# Connectors.net
KiCad netlist of a schematic drawn in Altium Designer
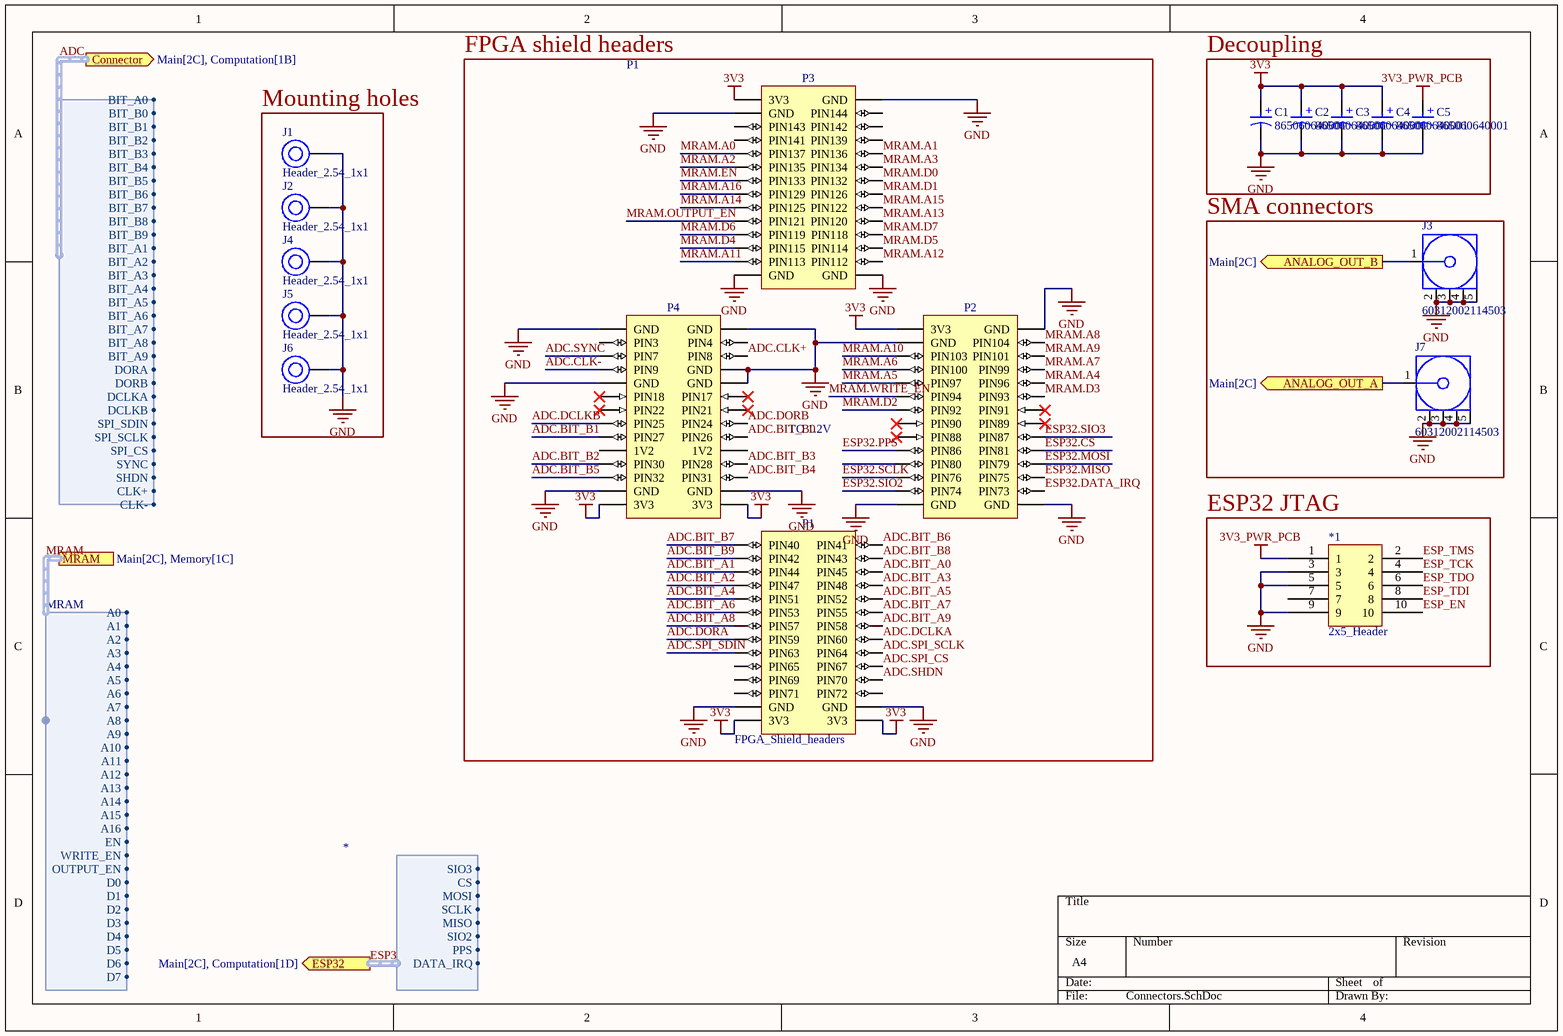
[diagram p0: Connectors.SchDoc]

(export (version "E")
  (design (tool "Eeschema 10.0.6"))
  (components
    (comp (ref "*1")
      (value "2x5_Header")
      (footprint "2x5_HEADER")
      (libsource (lib "Schlib1") (part "2x5_Header"))
    )
    (comp (ref "C1")
      (value "865060640001")
      (footprint "WCAP-ASLL_D4H5.5")
      (description "865060640001 WCAP-ASLL Aluminum Electrolytic Capacitors")
      (fields (field (name "TOLERANCE") "20%"))
      (libsource (lib "Altium Content Vault") (part "Capacitor_Polarized"))
    )
    (comp (ref "C2")
      (value "865060640001")
      (footprint "WCAP-ASLL_D4H5.5")
      (description "865060640001 WCAP-ASLL Aluminum Electrolytic Capacitors")
      (fields (field (name "TOLERANCE") "20%"))
      (libsource (lib "Altium Content Vault") (part "Capacitor_Polarized"))
    )
    (comp (ref "C3")
      (value "865060640001")
      (footprint "WCAP-ASLL_D4H5.5")
      (description "865060640001 WCAP-ASLL Aluminum Electrolytic Capacitors")
      (fields (field (name "TOLERANCE") "20%"))
      (libsource (lib "Altium Content Vault") (part "Capacitor_Polarized"))
    )
    (comp (ref "C4")
      (value "865060640001")
      (footprint "WCAP-ASLL_D4H5.5")
      (description "865060640001 WCAP-ASLL Aluminum Electrolytic Capacitors")
      (fields (field (name "TOLERANCE") "20%"))
      (libsource (lib "Altium Content Vault") (part "Capacitor_Polarized"))
    )
    (comp (ref "C5")
      (value "865060640001")
      (footprint "WCAP-ASLL_D4H5.5")
      (description "865060640001 WCAP-ASLL Aluminum Electrolytic Capacitors")
      (fields (field (name "TOLERANCE") "20%"))
      (libsource (lib "Altium Content Vault") (part "Capacitor_Polarized"))
    )
    (comp (ref "J1")
      (value "Header_2.54_1x1")
      (footprint "HEADER_2.54_1x1")
      (description "Header 1x1")
      (libsource (lib "Schlib1") (part "Header_2.54_1x1"))
    )
    (comp (ref "J2")
      (value "Header_2.54_1x1")
      (footprint "HEADER_2.54_1x1")
      (description "Header 1x1")
      (libsource (lib "Schlib1") (part "Header_2.54_1x1"))
    )
    (comp (ref "J3")
      (value "60312002114503")
      (footprint "60312002114503")
      (description "SMA PCB THT JACK STRAIGHT WR-SMA")
      (libsource (lib "Altium Content Vault") (part "Jack_4GND"))
    )
    (comp (ref "J4")
      (value "Header_2.54_1x1")
      (footprint "HEADER_2.54_1x1")
      (description "Header 1x1")
      (libsource (lib "Schlib1") (part "Header_2.54_1x1"))
    )
    (comp (ref "J5")
      (value "Header_2.54_1x1")
      (footprint "HEADER_2.54_1x1")
      (description "Header 1x1")
      (libsource (lib "Schlib1") (part "Header_2.54_1x1"))
    )
    (comp (ref "J6")
      (value "Header_2.54_1x1")
      (footprint "HEADER_2.54_1x1")
      (description "Header 1x1")
      (libsource (lib "Schlib1") (part "Header_2.54_1x1"))
    )
    (comp (ref "J7")
      (value "60312002114503")
      (footprint "60312002114503")
      (description "SMA PCB THT JACK STRAIGHT WR-SMA")
      (libsource (lib "Altium Content Vault") (part "Jack_4GND"))
    )
    (comp (ref "P1")
      (value "FPGA_Shield_headers")
      (footprint "FPGA_SHIELD_HEADER_FOOTPRINT")
      (libsource (lib "Schlib1") (part "FPGA_Shield_headers"))
    )
  )
  (nets
    (net (code "4") (name "/ADC.BIT_A0") (class "Default")
      (node (ref "P1") (pin "90") (pinfunction "PIN45_90") (pintype "bidirectional"))
    )
    (net (code "5") (name "/ADC.BIT_A1") (class "Default")
      (node (ref "P1") (pin "89") (pinfunction "PIN44_89") (pintype "bidirectional"))
    )
    (net (code "6") (name "/ADC.BIT_A2") (class "Default")
      (node (ref "P1") (pin "91") (pinfunction "PIN47_91") (pintype "bidirectional"))
    )
    (net (code "7") (name "/ADC.BIT_A3") (class "Default")
      (node (ref "P1") (pin "92") (pinfunction "PIN48_92") (pintype "bidirectional"))
    )
    (net (code "8") (name "/ADC.BIT_A4") (class "Default")
      (node (ref "P1") (pin "93") (pinfunction "PIN51_93") (pintype "bidirectional"))
    )
    (net (code "9") (name "/ADC.BIT_A5") (class "Default")
      (node (ref "P1") (pin "94") (pinfunction "PIN52_94") (pintype "bidirectional"))
    )
    (net (code "10") (name "/ADC.BIT_A6") (class "Default")
      (node (ref "P1") (pin "95") (pinfunction "PIN53_95") (pintype "bidirectional"))
    )
    (net (code "11") (name "/ADC.BIT_A7") (class "Default")
      (node (ref "P1") (pin "96") (pinfunction "PIN55_96") (pintype "bidirectional"))
    )
    (net (code "12") (name "/ADC.BIT_A8") (class "Default")
      (node (ref "P1") (pin "97") (pinfunction "PIN57_97") (pintype "bidirectional"))
    )
    (net (code "13") (name "/ADC.BIT_A9") (class "Default")
      (node (ref "P1") (pin "98") (pinfunction "PIN58_98") (pintype "bidirectional"))
    )
    (net (code "14") (name "/ADC.BIT_B0") (class "Default")
      (node (ref "P1") (pin "18") (pinfunction "PIN26_18") (pintype "bidirectional"))
    )
    (net (code "15") (name "/ADC.BIT_B1") (class "Default")
      (node (ref "P1") (pin "17") (pinfunction "PIN27_17") (pintype "bidirectional"))
    )
    (net (code "16") (name "/ADC.BIT_B2") (class "Default")
      (node (ref "P1") (pin "21") (pinfunction "PIN30_21") (pintype "bidirectional"))
    )
    (net (code "17") (name "/ADC.BIT_B3") (class "Default")
      (node (ref "P1") (pin "22") (pinfunction "PIN28_22") (pintype "bidirectional"))
    )
    (net (code "18") (name "/ADC.BIT_B4") (class "Default")
      (node (ref "P1") (pin "24") (pinfunction "PIN31_24") (pintype "bidirectional"))
    )
    (net (code "19") (name "/ADC.BIT_B5") (class "Default")
      (node (ref "P1") (pin "23") (pinfunction "PIN32_23") (pintype "bidirectional"))
    )
    (net (code "20") (name "/ADC.BIT_B6") (class "Default")
      (node (ref "P1") (pin "86") (pinfunction "PIN41_86") (pintype "bidirectional"))
    )
    (net (code "21") (name "/ADC.BIT_B7") (class "Default")
      (node (ref "P1") (pin "85") (pinfunction "PIN40_85") (pintype "bidirectional"))
    )
    (net (code "22") (name "/ADC.BIT_B8") (class "Default")
      (node (ref "P1") (pin "88") (pinfunction "PIN43_88") (pintype "bidirectional"))
    )
    (net (code "23") (name "/ADC.BIT_B9") (class "Default")
      (node (ref "P1") (pin "87") (pinfunction "PIN42_87") (pintype "bidirectional"))
    )
    (net (code "24") (name "/ADC.CLK+") (class "Default")
      (node (ref "P1") (pin "6") (pinfunction "PIN8_6") (pintype "bidirectional"))
    )
    (net (code "25") (name "/ADC.CLK-") (class "Default")
      (node (ref "P1") (pin "7") (pinfunction "PIN9_7") (pintype "bidirectional"))
    )
    (net (code "26") (name "/ADC.DCLKA") (class "Default")
      (node (ref "P1") (pin "100") (pinfunction "PIN60_100") (pintype "bidirectional"))
    )
    (net (code "27") (name "/ADC.DCLKB") (class "Default")
      (node (ref "P1") (pin "15") (pinfunction "PIN25_15") (pintype "bidirectional"))
    )
    (net (code "28") (name "/ADC.DORA") (class "Default")
      (node (ref "P1") (pin "99") (pinfunction "PIN59_99") (pintype "bidirectional"))
    )
    (net (code "29") (name "/ADC.DORB") (class "Default")
      (node (ref "P1") (pin "16") (pinfunction "PIN24_16") (pintype "bidirectional"))
    )
    (net (code "30") (name "/ADC.SHDN") (class "Default")
      (node (ref "P1") (pin "106") (pinfunction "PIN70_106") (pintype "bidirectional"))
    )
    (net (code "31") (name "/ADC.SPI_CS") (class "Default")
      (node (ref "P1") (pin "104") (pinfunction "PIN67_104") (pintype "bidirectional"))
    )
    (net (code "32") (name "/ADC.SPI_SCLK") (class "Default")
      (node (ref "P1") (pin "102") (pinfunction "PIN64_102") (pintype "bidirectional"))
    )
    (net (code "33") (name "/ADC.SPI_SDIN") (class "Default")
      (node (ref "P1") (pin "101") (pinfunction "PIN63_101") (pintype "bidirectional"))
    )
    (net (code "34") (name "/ADC.SYNC") (class "Default")
      (node (ref "P1") (pin "5") (pinfunction "PIN7_5") (pintype "bidirectional"))
    )
    (net (code "36") (name "/ANALOG_OUT_A") (class "Default")
      (node (ref "J7") (pin "1") (pinfunction "Signal_1") (pintype "passive"))
    )
    (net (code "37") (name "/ANALOG_OUT_B") (class "Default")
      (node (ref "J3") (pin "1") (pinfunction "Signal_1") (pintype "passive"))
    )
    (net (code "38") (name "/ESP32.CS") (class "Default")
      (node (ref "P1") (pin "76") (pinfunction "PIN81_76") (pintype "bidirectional"))
    )
    (net (code "39") (name "/ESP32.DATA_IRQ") (class "Default")
      (node (ref "P1") (pin "82") (pinfunction "PIN73_82") (pintype "bidirectional"))
    )
    (net (code "40") (name "/ESP32.MISO") (class "Default")
      (node (ref "P1") (pin "80") (pinfunction "PIN75_80") (pintype "bidirectional"))
    )
    (net (code "41") (name "/ESP32.MOSI") (class "Default")
      (node (ref "P1") (pin "78") (pinfunction "PIN79_78") (pintype "bidirectional"))
    )
    (net (code "42") (name "/ESP32.PPS") (class "Default")
      (node (ref "P1") (pin "75") (pinfunction "PIN86_75") (pintype "bidirectional"))
    )
    (net (code "43") (name "/ESP32.SCLK") (class "Default")
      (node (ref "P1") (pin "79") (pinfunction "PIN76_79") (pintype "bidirectional"))
    )
    (net (code "44") (name "/ESP32.SIO2") (class "Default")
      (node (ref "P1") (pin "81") (pinfunction "PIN74_81") (pintype "bidirectional"))
    )
    (net (code "45") (name "/ESP32.SIO3") (class "Default")
      (node (ref "P1") (pin "74") (pinfunction "PIN87_74") (pintype "bidirectional"))
    )
    (net (code "47") (name "/ESP_EN") (class "Default")
      (node (ref "*1") (pin "10") (pinfunction "10_10") (pintype "passive"))
    )
    (net (code "48") (name "/ESP_TCK") (class "Default")
      (node (ref "*1") (pin "4") (pinfunction "4_4") (pintype "passive"))
    )
    (net (code "49") (name "/ESP_TDI") (class "Default")
      (node (ref "*1") (pin "8") (pinfunction "8_8") (pintype "passive"))
    )
    (net (code "50") (name "/ESP_TDO") (class "Default")
      (node (ref "*1") (pin "6") (pinfunction "6_6") (pintype "passive"))
    )
    (net (code "51") (name "/ESP_TMS") (class "Default")
      (node (ref "*1") (pin "2") (pinfunction "2_2") (pintype "passive"))
    )
    (net (code "52") (name "/MRAM.A0") (class "Default")
      (node (ref "P1") (pin "37") (pinfunction "PIN137_37") (pintype "bidirectional"))
    )
    (net (code "53") (name "/MRAM.A1") (class "Default")
      (node (ref "P1") (pin "38") (pinfunction "PIN136_38") (pintype "bidirectional"))
    )
    (net (code "54") (name "/MRAM.A2") (class "Default")
      (node (ref "P1") (pin "39") (pinfunction "PIN135_39") (pintype "bidirectional"))
    )
    (net (code "55") (name "/MRAM.A3") (class "Default")
      (node (ref "P1") (pin "40") (pinfunction "PIN134_40") (pintype "bidirectional"))
    )
    (net (code "56") (name "/MRAM.A4") (class "Default")
      (node (ref "P1") (pin "66") (pinfunction "PIN96_66") (pintype "bidirectional"))
    )
    (net (code "57") (name "/MRAM.A5") (class "Default")
      (node (ref "P1") (pin "65") (pinfunction "PIN97_65") (pintype "bidirectional"))
    )
    (net (code "58") (name "/MRAM.A6") (class "Default")
      (node (ref "P1") (pin "63") (pinfunction "PIN100_63") (pintype "bidirectional"))
    )
    (net (code "59") (name "/MRAM.A7") (class "Default")
      (node (ref "P1") (pin "64") (pinfunction "PIN99_64") (pintype "bidirectional"))
    )
    (net (code "60") (name "/MRAM.A8") (class "Default")
      (node (ref "P1") (pin "60") (pinfunction "PIN104_60") (pintype "bidirectional"))
    )
    (net (code "61") (name "/MRAM.A9") (class "Default")
      (node (ref "P1") (pin "62") (pinfunction "PIN101_62") (pintype "bidirectional"))
    )
    (net (code "62") (name "/MRAM.A10") (class "Default")
      (node (ref "P1") (pin "61") (pinfunction "PIN103_61") (pintype "bidirectional"))
    )
    (net (code "63") (name "/MRAM.A11") (class "Default")
      (node (ref "P1") (pin "53") (pinfunction "PIN113_53") (pintype "bidirectional"))
    )
    (net (code "64") (name "/MRAM.A12") (class "Default")
      (node (ref "P1") (pin "54") (pinfunction "PIN112_54") (pintype "bidirectional"))
    )
    (net (code "65") (name "/MRAM.A13") (class "Default")
      (node (ref "P1") (pin "48") (pinfunction "PIN120_48") (pintype "bidirectional"))
    )
    (net (code "66") (name "/MRAM.A14") (class "Default")
      (node (ref "P1") (pin "45") (pinfunction "PIN125_45") (pintype "bidirectional"))
    )
    (net (code "67") (name "/MRAM.A15") (class "Default")
      (node (ref "P1") (pin "46") (pinfunction "PIN122_46") (pintype "bidirectional"))
    )
    (net (code "68") (name "/MRAM.A16") (class "Default")
      (node (ref "P1") (pin "43") (pinfunction "PIN129_43") (pintype "bidirectional"))
    )
    (net (code "69") (name "/MRAM.D0") (class "Default")
      (node (ref "P1") (pin "42") (pinfunction "PIN132_42") (pintype "bidirectional"))
    )
    (net (code "70") (name "/MRAM.D1") (class "Default")
      (node (ref "P1") (pin "44") (pinfunction "PIN126_44") (pintype "bidirectional"))
    )
    (net (code "71") (name "/MRAM.D2") (class "Default")
      (node (ref "P1") (pin "69") (pinfunction "PIN92_69") (pintype "bidirectional"))
    )
    (net (code "72") (name "/MRAM.D3") (class "Default")
      (node (ref "P1") (pin "68") (pinfunction "PIN93_68") (pintype "bidirectional"))
    )
    (net (code "73") (name "/MRAM.D4") (class "Default")
      (node (ref "P1") (pin "51") (pinfunction "PIN115_51") (pintype "bidirectional"))
    )
    (net (code "74") (name "/MRAM.D5") (class "Default")
      (node (ref "P1") (pin "52") (pinfunction "PIN114_52") (pintype "bidirectional"))
    )
    (net (code "75") (name "/MRAM.D6") (class "Default")
      (node (ref "P1") (pin "49") (pinfunction "PIN119_49") (pintype "bidirectional"))
    )
    (net (code "76") (name "/MRAM.D7") (class "Default")
      (node (ref "P1") (pin "50") (pinfunction "PIN118_50") (pintype "bidirectional"))
    )
    (net (code "77") (name "/MRAM.EN") (class "Default")
      (node (ref "P1") (pin "41") (pinfunction "PIN133_41") (pintype "bidirectional"))
    )
    (net (code "78") (name "/MRAM.OUTPUT_EN") (class "Default")
      (node (ref "P1") (pin "47") (pinfunction "PIN121_47") (pintype "bidirectional"))
    )
    (net (code "79") (name "/MRAM.WRITE_EN") (class "Default")
      (node (ref "P1") (pin "67") (pinfunction "PIN94_67") (pintype "bidirectional"))
    )
    (net (code "81") (name "3V3") (class "Default")
      (node (ref "C1") (pin "1") (pinfunction "P_1") (pintype "passive"))
      (node (ref "C2") (pin "1") (pinfunction "P_1") (pintype "passive"))
      (node (ref "C3") (pin "1") (pinfunction "P_1") (pintype "passive"))
      (node (ref "C4") (pin "1") (pinfunction "P_1") (pintype "passive"))
      (node (ref "P1") (pin "111") (pinfunction "3V3_111") (pintype "passive"))
      (node (ref "P1") (pin "112") (pinfunction "3V3_112") (pintype "passive"))
      (node (ref "P1") (pin "27") (pinfunction "3V3_27") (pintype "passive"))
      (node (ref "P1") (pin "28") (pinfunction "3V3_28") (pintype "passive"))
      (node (ref "P1") (pin "29") (pinfunction "3V3_29") (pintype "passive"))
      (node (ref "P1") (pin "57") (pinfunction "3V3_57") (pintype "passive"))
    )
    (net (code "82") (name "3V3_PWR_PCB") (class "Default")
      (node (ref "*1") (pin "1") (pinfunction "1_1") (pintype "passive"))
      (node (ref "C5") (pin "1") (pinfunction "P_1") (pintype "passive"))
    )
    (net (code "83") (name "GND") (class "Default")
      (node (ref "*1") (pin "3") (pinfunction "3_3") (pintype "passive"))
      (node (ref "*1") (pin "5") (pinfunction "5_5") (pintype "passive"))
      (node (ref "*1") (pin "9") (pinfunction "9_9") (pintype "passive"))
      (node (ref "C1") (pin "2") (pinfunction "N_2") (pintype "passive"))
      (node (ref "C2") (pin "2") (pinfunction "N_2") (pintype "passive"))
      (node (ref "C3") (pin "2") (pinfunction "N_2") (pintype "passive"))
      (node (ref "C4") (pin "2") (pinfunction "N_2") (pintype "passive"))
      (node (ref "C5") (pin "2") (pinfunction "N_2") (pintype "passive"))
      (node (ref "J1") (pin "0") (pinfunction "0_0") (pintype "passive"))
      (node (ref "J2") (pin "0") (pinfunction "0_0") (pintype "passive"))
      (node (ref "J3") (pin "2") (pinfunction "GND_2") (pintype "passive"))
      (node (ref "J3") (pin "3") (pinfunction "GND_3") (pintype "passive"))
      (node (ref "J3") (pin "4") (pinfunction "GND_4") (pintype "passive"))
      (node (ref "J3") (pin "5") (pinfunction "GND_5") (pintype "passive"))
      (node (ref "J4") (pin "0") (pinfunction "0_0") (pintype "passive"))
      (node (ref "J5") (pin "0") (pinfunction "0_0") (pintype "passive"))
      (node (ref "J6") (pin "0") (pinfunction "0_0") (pintype "passive"))
      (node (ref "J7") (pin "2") (pinfunction "GND_2") (pintype "passive"))
      (node (ref "J7") (pin "3") (pinfunction "GND_3") (pintype "passive"))
      (node (ref "J7") (pin "4") (pinfunction "GND_4") (pintype "passive"))
      (node (ref "J7") (pin "5") (pinfunction "GND_5") (pintype "passive"))
      (node (ref "P1") (pin "1") (pinfunction "GND_1") (pintype "power_in"))
      (node (ref "P1") (pin "10") (pinfunction "GND_10") (pintype "passive"))
      (node (ref "P1") (pin "109") (pinfunction "GND_109") (pintype "passive"))
      (node (ref "P1") (pin "110") (pinfunction "GND_110") (pintype "passive"))
      (node (ref "P1") (pin "2") (pinfunction "GND_2") (pintype "power_in"))
      (node (ref "P1") (pin "25") (pinfunction "GND_25") (pintype "passive"))
      (node (ref "P1") (pin "26") (pinfunction "GND_26") (pintype "passive"))
      (node (ref "P1") (pin "30") (pinfunction "GND_30") (pintype "passive"))
      (node (ref "P1") (pin "31") (pinfunction "GND_31") (pintype "passive"))
      (node (ref "P1") (pin "55") (pinfunction "GND_55") (pintype "passive"))
      (node (ref "P1") (pin "56") (pinfunction "GND_56") (pintype "passive"))
      (node (ref "P1") (pin "58") (pinfunction "GND_58") (pintype "passive"))
      (node (ref "P1") (pin "59") (pinfunction "GND_59") (pintype "passive"))
      (node (ref "P1") (pin "8") (pinfunction "GND_8") (pintype "passive"))
      (node (ref "P1") (pin "83") (pinfunction "GND_83") (pintype "passive"))
      (node (ref "P1") (pin "84") (pinfunction "GND_84") (pintype "passive"))
      (node (ref "P1") (pin "9") (pinfunction "GND_9") (pintype "passive"))
    )
    (net (code "84") (name "unconnected-(*1-Pad7)") (class "Default")
      (node (ref "*1") (pin "7") (pinfunction "7_7") (pintype "passive"))
    )
    (net (code "85") (name "unconnected-(P1-1V2-Pad19)") (class "Default")
      (node (ref "P1") (pin "19") (pinfunction "1V2_19") (pintype "passive"))
    )
    (net (code "86") (name "unconnected-(P1-1V2-Pad20)") (class "Default")
      (node (ref "P1") (pin "20") (pinfunction "1V2_20") (pintype "passive"))
    )
    (net (code "87") (name "unconnected-(P1-PIN3-Pad3)") (class "Default")
      (node (ref "P1") (pin "3") (pinfunction "PIN3_3") (pintype "bidirectional"))
    )
    (net (code "88") (name "unconnected-(P1-PIN4-Pad4)") (class "Default")
      (node (ref "P1") (pin "4") (pinfunction "PIN4_4") (pintype "bidirectional"))
    )
    (net (code "89") (name "unconnected-(P1-PIN17-Pad12)") (class "Default")
      (node (ref "P1") (pin "12") (pinfunction "PIN17_12") (pintype "input+no_connect"))
    )
    (net (code "90") (name "unconnected-(P1-PIN18-Pad11)") (class "Default")
      (node (ref "P1") (pin "11") (pinfunction "PIN18_11") (pintype "input+no_connect"))
    )
    (net (code "91") (name "unconnected-(P1-PIN21-Pad14)") (class "Default")
      (node (ref "P1") (pin "14") (pinfunction "PIN21_14") (pintype "input+no_connect"))
    )
    (net (code "92") (name "unconnected-(P1-PIN22-Pad13)") (class "Default")
      (node (ref "P1") (pin "13") (pinfunction "PIN22_13") (pintype "input+no_connect"))
    )
    (net (code "93") (name "unconnected-(P1-PIN65-Pad103)") (class "Default")
      (node (ref "P1") (pin "103") (pinfunction "PIN65_103") (pintype "bidirectional"))
    )
    (net (code "94") (name "unconnected-(P1-PIN69-Pad105)") (class "Default")
      (node (ref "P1") (pin "105") (pinfunction "PIN69_105") (pintype "bidirectional"))
    )
    (net (code "95") (name "unconnected-(P1-PIN71-Pad107)") (class "Default")
      (node (ref "P1") (pin "107") (pinfunction "PIN71_107") (pintype "bidirectional"))
    )
    (net (code "96") (name "unconnected-(P1-PIN72-Pad108)") (class "Default")
      (node (ref "P1") (pin "108") (pinfunction "PIN72_108") (pintype "bidirectional"))
    )
    (net (code "97") (name "unconnected-(P1-PIN80-Pad77)") (class "Default")
      (node (ref "P1") (pin "77") (pinfunction "PIN80_77") (pintype "bidirectional"))
    )
    (net (code "98") (name "unconnected-(P1-PIN88-Pad73)") (class "Default")
      (node (ref "P1") (pin "73") (pinfunction "PIN88_73") (pintype "input+no_connect"))
    )
    (net (code "99") (name "unconnected-(P1-PIN89-Pad72)") (class "Default")
      (node (ref "P1") (pin "72") (pinfunction "PIN89_72") (pintype "input+no_connect"))
    )
    (net (code "100") (name "unconnected-(P1-PIN90-Pad71)") (class "Default")
      (node (ref "P1") (pin "71") (pinfunction "PIN90_71") (pintype "input+no_connect"))
    )
    (net (code "101") (name "unconnected-(P1-PIN91-Pad70)") (class "Default")
      (node (ref "P1") (pin "70") (pinfunction "PIN91_70") (pintype "input+no_connect"))
    )
    (net (code "102") (name "unconnected-(P1-PIN139-Pad36)") (class "Default")
      (node (ref "P1") (pin "36") (pinfunction "PIN139_36") (pintype "bidirectional"))
    )
    (net (code "103") (name "unconnected-(P1-PIN141-Pad35)") (class "Default")
      (node (ref "P1") (pin "35") (pinfunction "PIN141_35") (pintype "bidirectional"))
    )
    (net (code "104") (name "unconnected-(P1-PIN142-Pad34)") (class "Default")
      (node (ref "P1") (pin "34") (pinfunction "PIN142_34") (pintype "bidirectional"))
    )
    (net (code "105") (name "unconnected-(P1-PIN143-Pad33)") (class "Default")
      (node (ref "P1") (pin "33") (pinfunction "PIN143_33") (pintype "bidirectional"))
    )
    (net (code "106") (name "unconnected-(P1-PIN144-Pad32)") (class "Default")
      (node (ref "P1") (pin "32") (pinfunction "PIN144_32") (pintype "bidirectional"))
    )
  )
)
